# ADM3202_conv.net
KiCad netlist of a schematic drawn in EAGLE
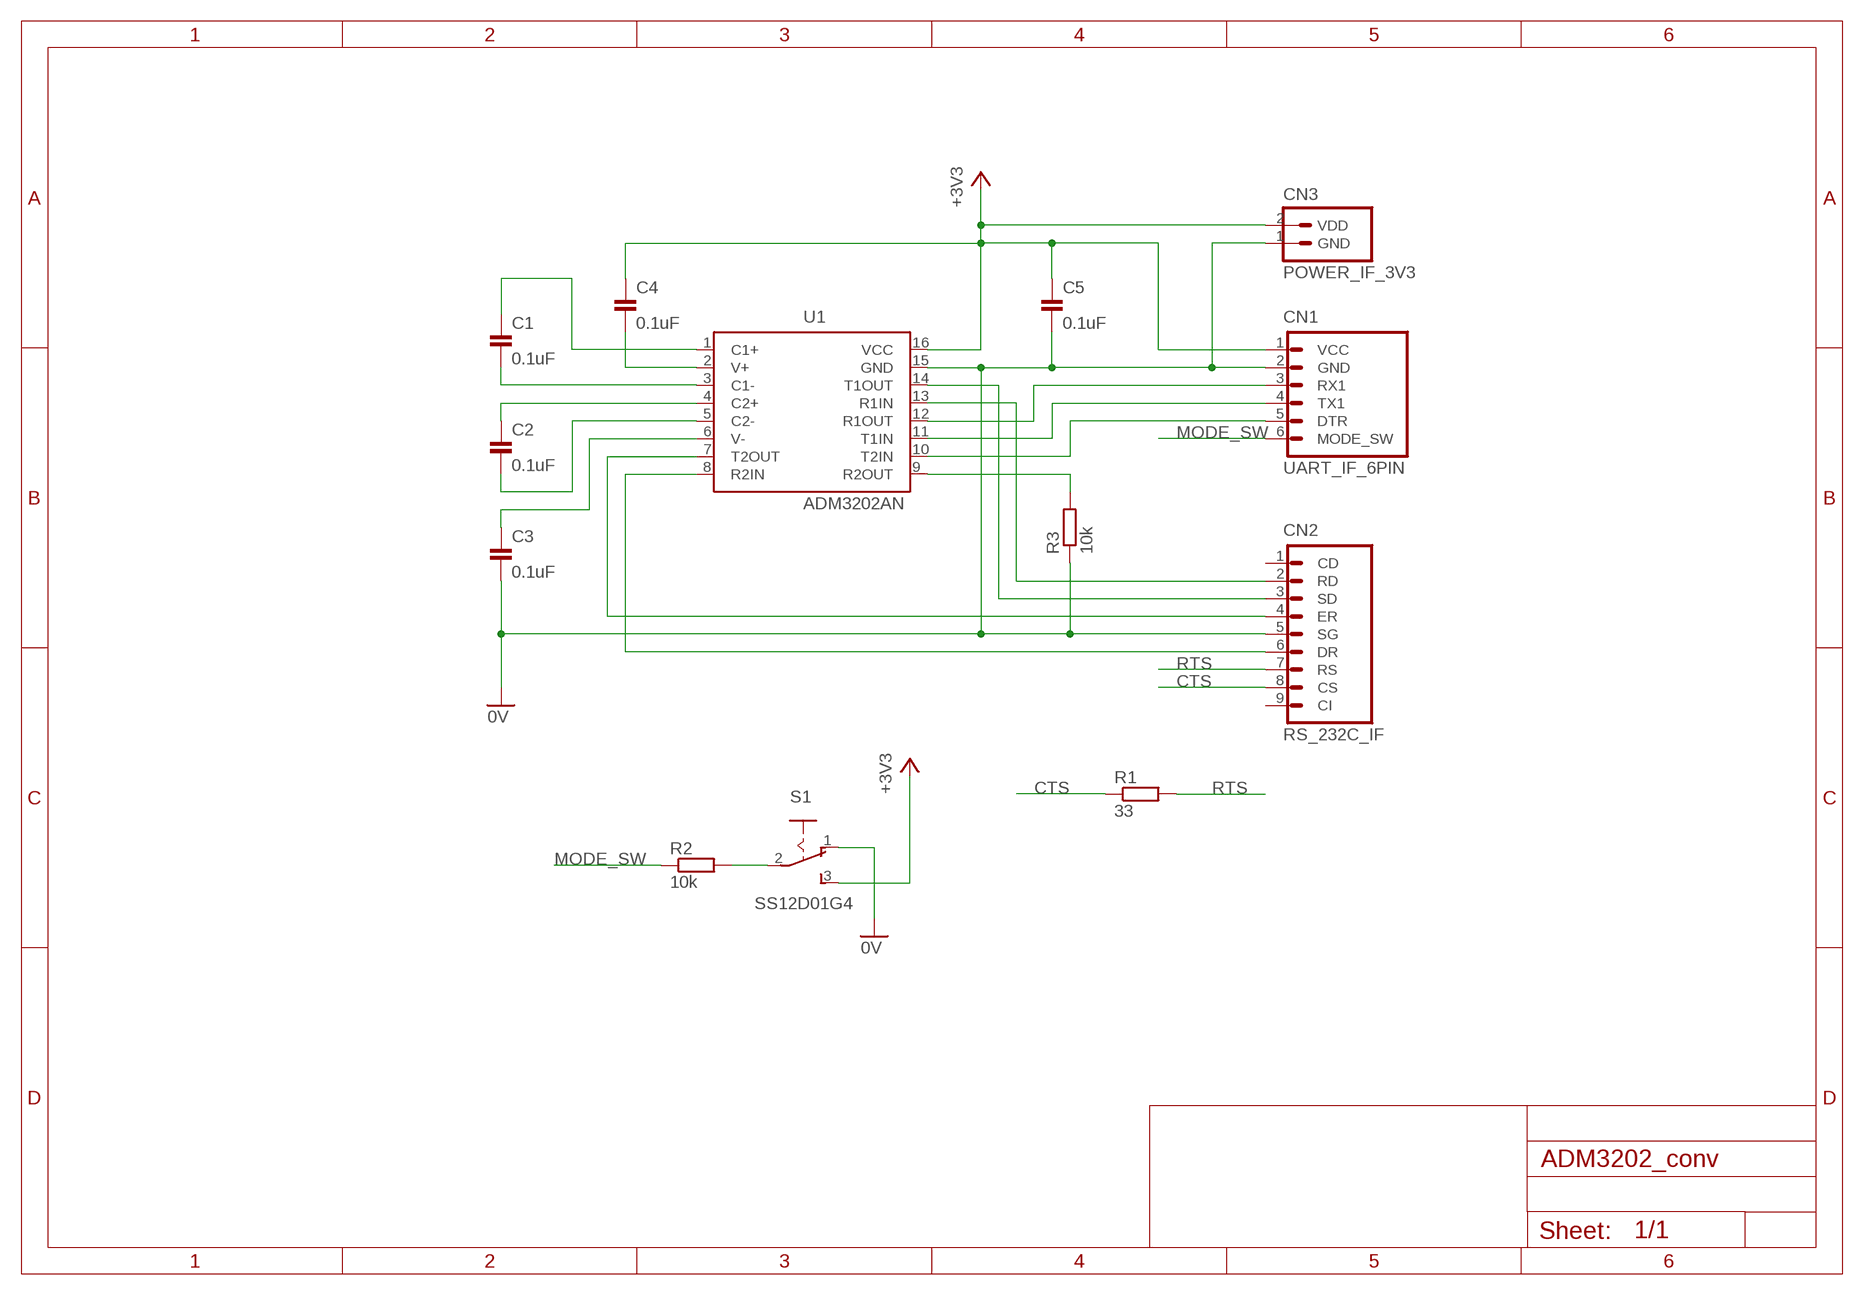
[diagram p0: schematic, sheet 1]

(export (version "E")
  (design (tool "Eeschema 10.0.6"))
  (components
    (comp (ref "C1")
      (value "0.1uF")
      (footprint "eagle-import:SMD_2012_DEV")
      (libsource (lib "eagle-import") (part "CAP_0805_DEV"))
    )
    (comp (ref "C2")
      (value "0.1uF")
      (footprint "eagle-import:SMD_2012_DEV")
      (libsource (lib "eagle-import") (part "CAP_0805_DEV"))
    )
    (comp (ref "C3")
      (value "0.1uF")
      (footprint "eagle-import:SMD_2012_DEV")
      (libsource (lib "eagle-import") (part "CAP_0805_DEV"))
    )
    (comp (ref "C4")
      (value "0.1uF")
      (footprint "eagle-import:SMD_2012_DEV")
      (libsource (lib "eagle-import") (part "CAP_0805_DEV"))
    )
    (comp (ref "C5")
      (value "0.1uF")
      (footprint "eagle-import:SMD_2012_DEV")
      (libsource (lib "eagle-import") (part "CAP_0805_DEV"))
    )
    (comp (ref "CN1")
      (value "UART_IF_6PIN")
      (footprint "eagle-import:UART_IF_6PIN")
      (libsource (lib "eagle-import") (part "UART_IF_6PIN"))
    )
    (comp (ref "CN2")
      (value "RS_232C_IF")
      (footprint "eagle-import:UM04_RS_232C_IF_9PIN")
      (libsource (lib "eagle-import") (part "UM04_RS_232C_IF"))
    )
    (comp (ref "CN3")
      (value "POWER_IF_3V3")
      (footprint "eagle-import:HEADER_2PIN_3V3_IF")
      (libsource (lib "eagle-import") (part "POWER_IF_3V3"))
    )
    (comp (ref "R1")
      (value "33")
      (footprint "eagle-import:RESISTOR_0207_300MIL")
      (libsource (lib "eagle-import") (part "RESISTOR_300MIL"))
    )
    (comp (ref "R2")
      (value "10k")
      (footprint "eagle-import:SMD_2012_DEV")
      (libsource (lib "eagle-import") (part "RESISTOR_0805_DEV"))
    )
    (comp (ref "R3")
      (value "10k")
      (footprint "eagle-import:SMD_2012_DEV")
      (libsource (lib "eagle-import") (part "RESISTOR_0805_DEV"))
    )
    (comp (ref "S1")
      (value "SS12D01G4")
      (footprint "eagle-import:SLIDE_SWITCH_1C")
      (libsource (lib "eagle-import") (part "SS12D01G4"))
    )
    (comp (ref "U1")
      (value "ADM3202AN")
      (footprint "eagle-import:DIL16")
      (libsource (lib "eagle-import") (part "ADM3202AN"))
    )
  )
  (nets
    (net (code "1") (name "+3V3") (class "Default")
      (node (ref "C4") (pin "1") (pinfunction "1_1") (pintype "passive"))
      (node (ref "C5") (pin "1") (pinfunction "1_1") (pintype "passive"))
      (node (ref "CN1") (pin "1") (pinfunction "VCC_1") (pintype "passive"))
      (node (ref "CN3") (pin "2") (pinfunction "VDD_2") (pintype "passive"))
      (node (ref "S1") (pin "3") (pinfunction "S_3") (pintype "passive"))
      (node (ref "U1") (pin "16") (pinfunction "VCC_16") (pintype "passive"))
    )
    (net (code "2") (name "/CTS") (class "Default")
      (node (ref "CN2") (pin "8") (pinfunction "CS_8") (pintype "bidirectional"))
      (node (ref "R1") (pin "1") (pinfunction "1_1") (pintype "passive"))
    )
    (net (code "3") (name "/MODE_SW") (class "Default")
      (node (ref "CN1") (pin "6") (pinfunction "MODE_SW_6") (pintype "bidirectional"))
      (node (ref "R2") (pin "1") (pinfunction "1_1") (pintype "passive"))
    )
    (net (code "4") (name "/RTS") (class "Default")
      (node (ref "CN2") (pin "7") (pinfunction "RS_7") (pintype "bidirectional"))
      (node (ref "R1") (pin "2") (pinfunction "2_2") (pintype "passive"))
    )
    (net (code "5") (name "0V") (class "Default")
      (node (ref "C3") (pin "2") (pinfunction "2_2") (pintype "passive"))
      (node (ref "C5") (pin "2") (pinfunction "2_2") (pintype "passive"))
      (node (ref "CN1") (pin "2") (pinfunction "GND_2") (pintype "passive"))
      (node (ref "CN2") (pin "5") (pinfunction "SG_5") (pintype "passive"))
      (node (ref "CN3") (pin "1") (pinfunction "GND_1") (pintype "passive"))
      (node (ref "R3") (pin "1") (pinfunction "1_1") (pintype "passive"))
      (node (ref "S1") (pin "1") (pinfunction "O_1") (pintype "passive"))
      (node (ref "U1") (pin "15") (pinfunction "GND_15") (pintype "passive"))
    )
    (net (code "6") (name "Net-(CN1-DTR)") (class "Default")
      (node (ref "CN1") (pin "5") (pinfunction "DTR_5") (pintype "bidirectional"))
      (node (ref "U1") (pin "10") (pinfunction "T2IN_10") (pintype "bidirectional"))
    )
    (net (code "7") (name "Net-(CN1-RX1)") (class "Default")
      (node (ref "CN1") (pin "3") (pinfunction "RX1_3") (pintype "bidirectional"))
      (node (ref "U1") (pin "12") (pinfunction "R1OUT_12") (pintype "bidirectional"))
    )
    (net (code "8") (name "Net-(CN1-TX1)") (class "Default")
      (node (ref "CN1") (pin "4") (pinfunction "TX1_4") (pintype "bidirectional"))
      (node (ref "U1") (pin "11") (pinfunction "T1IN_11") (pintype "bidirectional"))
    )
    (net (code "9") (name "Net-(CN2-DR)") (class "Default")
      (node (ref "CN2") (pin "6") (pinfunction "DR_6") (pintype "bidirectional"))
      (node (ref "U1") (pin "8") (pinfunction "R2IN_8") (pintype "bidirectional"))
    )
    (net (code "10") (name "Net-(CN2-ER)") (class "Default")
      (node (ref "CN2") (pin "4") (pinfunction "ER_4") (pintype "bidirectional"))
      (node (ref "U1") (pin "7") (pinfunction "T2OUT_7") (pintype "bidirectional"))
    )
    (net (code "11") (name "Net-(CN2-RD)") (class "Default")
      (node (ref "CN2") (pin "2") (pinfunction "RD_2") (pintype "bidirectional"))
      (node (ref "U1") (pin "13") (pinfunction "R1IN_13") (pintype "bidirectional"))
    )
    (net (code "12") (name "Net-(CN2-SD)") (class "Default")
      (node (ref "CN2") (pin "3") (pinfunction "SD_3") (pintype "bidirectional"))
      (node (ref "U1") (pin "14") (pinfunction "T1OUT_14") (pintype "bidirectional"))
    )
    (net (code "13") (name "Net-(S1-P)") (class "Default")
      (node (ref "R2") (pin "2") (pinfunction "2_2") (pintype "passive"))
      (node (ref "S1") (pin "2") (pinfunction "P_2") (pintype "passive"))
    )
    (net (code "14") (name "Net-(U1-C1+)") (class "Default")
      (node (ref "C1") (pin "1") (pinfunction "1_1") (pintype "passive"))
      (node (ref "U1") (pin "1") (pinfunction "C1+_1") (pintype "passive"))
    )
    (net (code "15") (name "Net-(U1-C1-)") (class "Default")
      (node (ref "C1") (pin "2") (pinfunction "2_2") (pintype "passive"))
      (node (ref "U1") (pin "3") (pinfunction "C1-_3") (pintype "passive"))
    )
    (net (code "16") (name "Net-(U1-C2+)") (class "Default")
      (node (ref "C2") (pin "1") (pinfunction "1_1") (pintype "passive"))
      (node (ref "U1") (pin "4") (pinfunction "C2+_4") (pintype "passive"))
    )
    (net (code "17") (name "Net-(U1-C2-)") (class "Default")
      (node (ref "C2") (pin "2") (pinfunction "2_2") (pintype "passive"))
      (node (ref "U1") (pin "5") (pinfunction "C2-_5") (pintype "passive"))
    )
    (net (code "18") (name "Net-(U1-R2OUT)") (class "Default")
      (node (ref "R3") (pin "2") (pinfunction "2_2") (pintype "passive"))
      (node (ref "U1") (pin "9") (pinfunction "R2OUT_9") (pintype "bidirectional"))
    )
    (net (code "19") (name "Net-(U1-V+)") (class "Default")
      (node (ref "C4") (pin "2") (pinfunction "2_2") (pintype "passive"))
      (node (ref "U1") (pin "2") (pinfunction "V+_2") (pintype "passive"))
    )
    (net (code "20") (name "Net-(U1-V-)") (class "Default")
      (node (ref "C3") (pin "1") (pinfunction "1_1") (pintype "passive"))
      (node (ref "U1") (pin "6") (pinfunction "V-_6") (pintype "passive"))
    )
    (net (code "21") (name "unconnected-(CN2-CD-Pad1)") (class "Default")
      (node (ref "CN2") (pin "1") (pinfunction "CD_1") (pintype "bidirectional"))
    )
    (net (code "22") (name "unconnected-(CN2-CI-Pad9)") (class "Default")
      (node (ref "CN2") (pin "9") (pinfunction "CI_9") (pintype "bidirectional"))
    )
  )
)
